# lpc_telem.net
KiCad netlist of a schematic drawn in Altium Designer
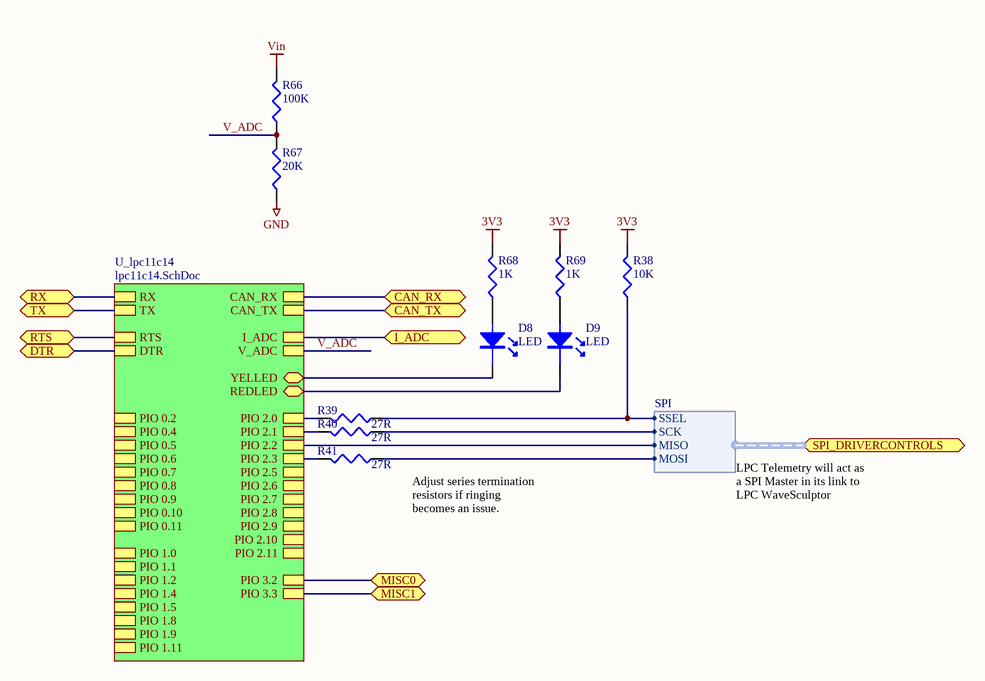
[diagram p0: lpc_telem.SchDoc]

(export (version "E")
  (design (tool "Eeschema 10.0.6"))
  (components
    (comp (ref "D8")
      (value "LED")
      (footprint "0805LED")
      (description "LED CHIPLED 588NM YLW 0805 SMD")
      (fields
        (field (name "MANUFACTURER") "OSRAM Opto Semiconductors Inc")
        (field (name "MANUFACTURER PART NUMBER") "LY R976-PS-36")
      )
      (libsource (lib "RCLDQ") (part "LED"))
    )
    (comp (ref "D9")
      (value "LED")
      (footprint "0805LED")
      (description "LED CHIPLED 633NM RED 0805 SMD")
      (fields
        (field (name "MANUFACTURER") "OSRAM Opto Semiconductors Inc")
        (field (name "MANUFACTURER PART NUMBER") "LS R976-NR-1")
      )
      (libsource (lib "RCLDQ") (part "LED"))
    )
    (comp (ref "R38")
      (value "10K")
      (footprint "0603")
      (description "Resistor")
      (libsource (lib "RCLDQ") (part "RES1"))
    )
    (comp (ref "R39")
      (value "27R")
      (footprint "0603")
      (description "Resistor")
      (fields
        (field (name "MANUFACTURER") "Panasonic Electronic Components")
        (field (name "MANUFACTURER PART NUMBER") "ERJ-3EKF27R0V")
      )
      (libsource (lib "RCLDQ") (part "RES1"))
    )
    (comp (ref "R40")
      (value "27R")
      (footprint "0603")
      (description "Resistor")
      (fields
        (field (name "MANUFACTURER") "Panasonic Electronic Components")
        (field (name "MANUFACTURER PART NUMBER") "ERJ-3EKF27R0V")
      )
      (libsource (lib "RCLDQ") (part "RES1"))
    )
    (comp (ref "R41")
      (value "27R")
      (footprint "0603")
      (description "Resistor")
      (fields
        (field (name "MANUFACTURER") "Panasonic Electronic Components")
        (field (name "MANUFACTURER PART NUMBER") "ERJ-3EKF27R0V")
      )
      (libsource (lib "RCLDQ") (part "RES1"))
    )
    (comp (ref "R66")
      (value "100K")
      (footprint "0603")
      (description "Resistor")
      (fields
        (field (name "MANUFACTURER") "Panasonic Electronic Components")
        (field (name "MANUFACTURER PART NUMBER") "ERJ-3EKF1003V")
      )
      (libsource (lib "2009_BatteryMaster") (part "RES1"))
    )
    (comp (ref "R67")
      (value "20K")
      (footprint "0603")
      (description "Resistor")
      (fields
        (field (name "MANUFACTURER") "Panasonic Electronic Components")
        (field (name "MANUFACTURER PART NUMBER") "ERJ-3EKF2002V")
      )
      (libsource (lib "2009_BatteryMaster") (part "RES1"))
    )
    (comp (ref "R68")
      (value "1K")
      (footprint "0603")
      (description "Resistor")
      (libsource (lib "RCLDQ") (part "RES1"))
    )
    (comp (ref "R69")
      (value "1K")
      (footprint "0603")
      (description "Resistor")
      (libsource (lib "RCLDQ") (part "RES1"))
    )
  )
  (nets
    (net (code "9") (name "/MOSI") (class "Default")
      (node (ref "R41") (pin "1") (pinfunction "1_1") (pintype "passive"))
    )
    (net (code "27") (name "/PIO 2.0") (class "Default")
      (node (ref "R39") (pin "2") (pinfunction "2_2") (pintype "passive"))
    )
    (net (code "28") (name "/PIO 2.1") (class "Default")
      (node (ref "R40") (pin "2") (pinfunction "2_2") (pintype "passive"))
    )
    (net (code "29") (name "/PIO 2.3") (class "Default")
      (node (ref "R41") (pin "2") (pinfunction "2_2") (pintype "passive"))
    )
    (net (code "37") (name "/REDLED") (class "Default")
      (node (ref "D9") (pin "K") (pinfunction "K_K") (pintype "passive"))
    )
    (net (code "40") (name "/SCK") (class "Default")
      (node (ref "R40") (pin "1") (pinfunction "1_1") (pintype "passive"))
    )
    (net (code "41") (name "/SSEL") (class "Default")
      (node (ref "R38") (pin "1") (pinfunction "1_1") (pintype "passive"))
      (node (ref "R39") (pin "1") (pinfunction "1_1") (pintype "passive"))
    )
    (net (code "43") (name "/V_ADC") (class "Default")
      (node (ref "R66") (pin "1") (pinfunction "1_1") (pintype "passive"))
      (node (ref "R67") (pin "2") (pinfunction "2_2") (pintype "passive"))
    )
    (net (code "44") (name "/YELLED") (class "Default")
      (node (ref "D8") (pin "K") (pinfunction "K_K") (pintype "passive"))
    )
    (net (code "46") (name "3V3") (class "Default")
      (node (ref "R38") (pin "2") (pinfunction "2_2") (pintype "passive"))
      (node (ref "R68") (pin "2") (pinfunction "2_2") (pintype "passive"))
      (node (ref "R69") (pin "2") (pinfunction "2_2") (pintype "passive"))
    )
    (net (code "47") (name "GND") (class "Default")
      (node (ref "R67") (pin "1") (pinfunction "1_1") (pintype "passive"))
    )
    (net (code "48") (name "Net-(D8-PadA)") (class "Default")
      (node (ref "D8") (pin "A") (pinfunction "A_A") (pintype "passive"))
      (node (ref "R68") (pin "1") (pinfunction "1_1") (pintype "passive"))
    )
    (net (code "49") (name "Net-(D9-PadA)") (class "Default")
      (node (ref "D9") (pin "A") (pinfunction "A_A") (pintype "passive"))
      (node (ref "R69") (pin "1") (pinfunction "1_1") (pintype "passive"))
    )
    (net (code "50") (name "Vin") (class "Default")
      (node (ref "R66") (pin "2") (pinfunction "2_2") (pintype "passive"))
    )
  )
)
